# Sheet1.net
KiCad netlist of a schematic drawn in Altium Designer
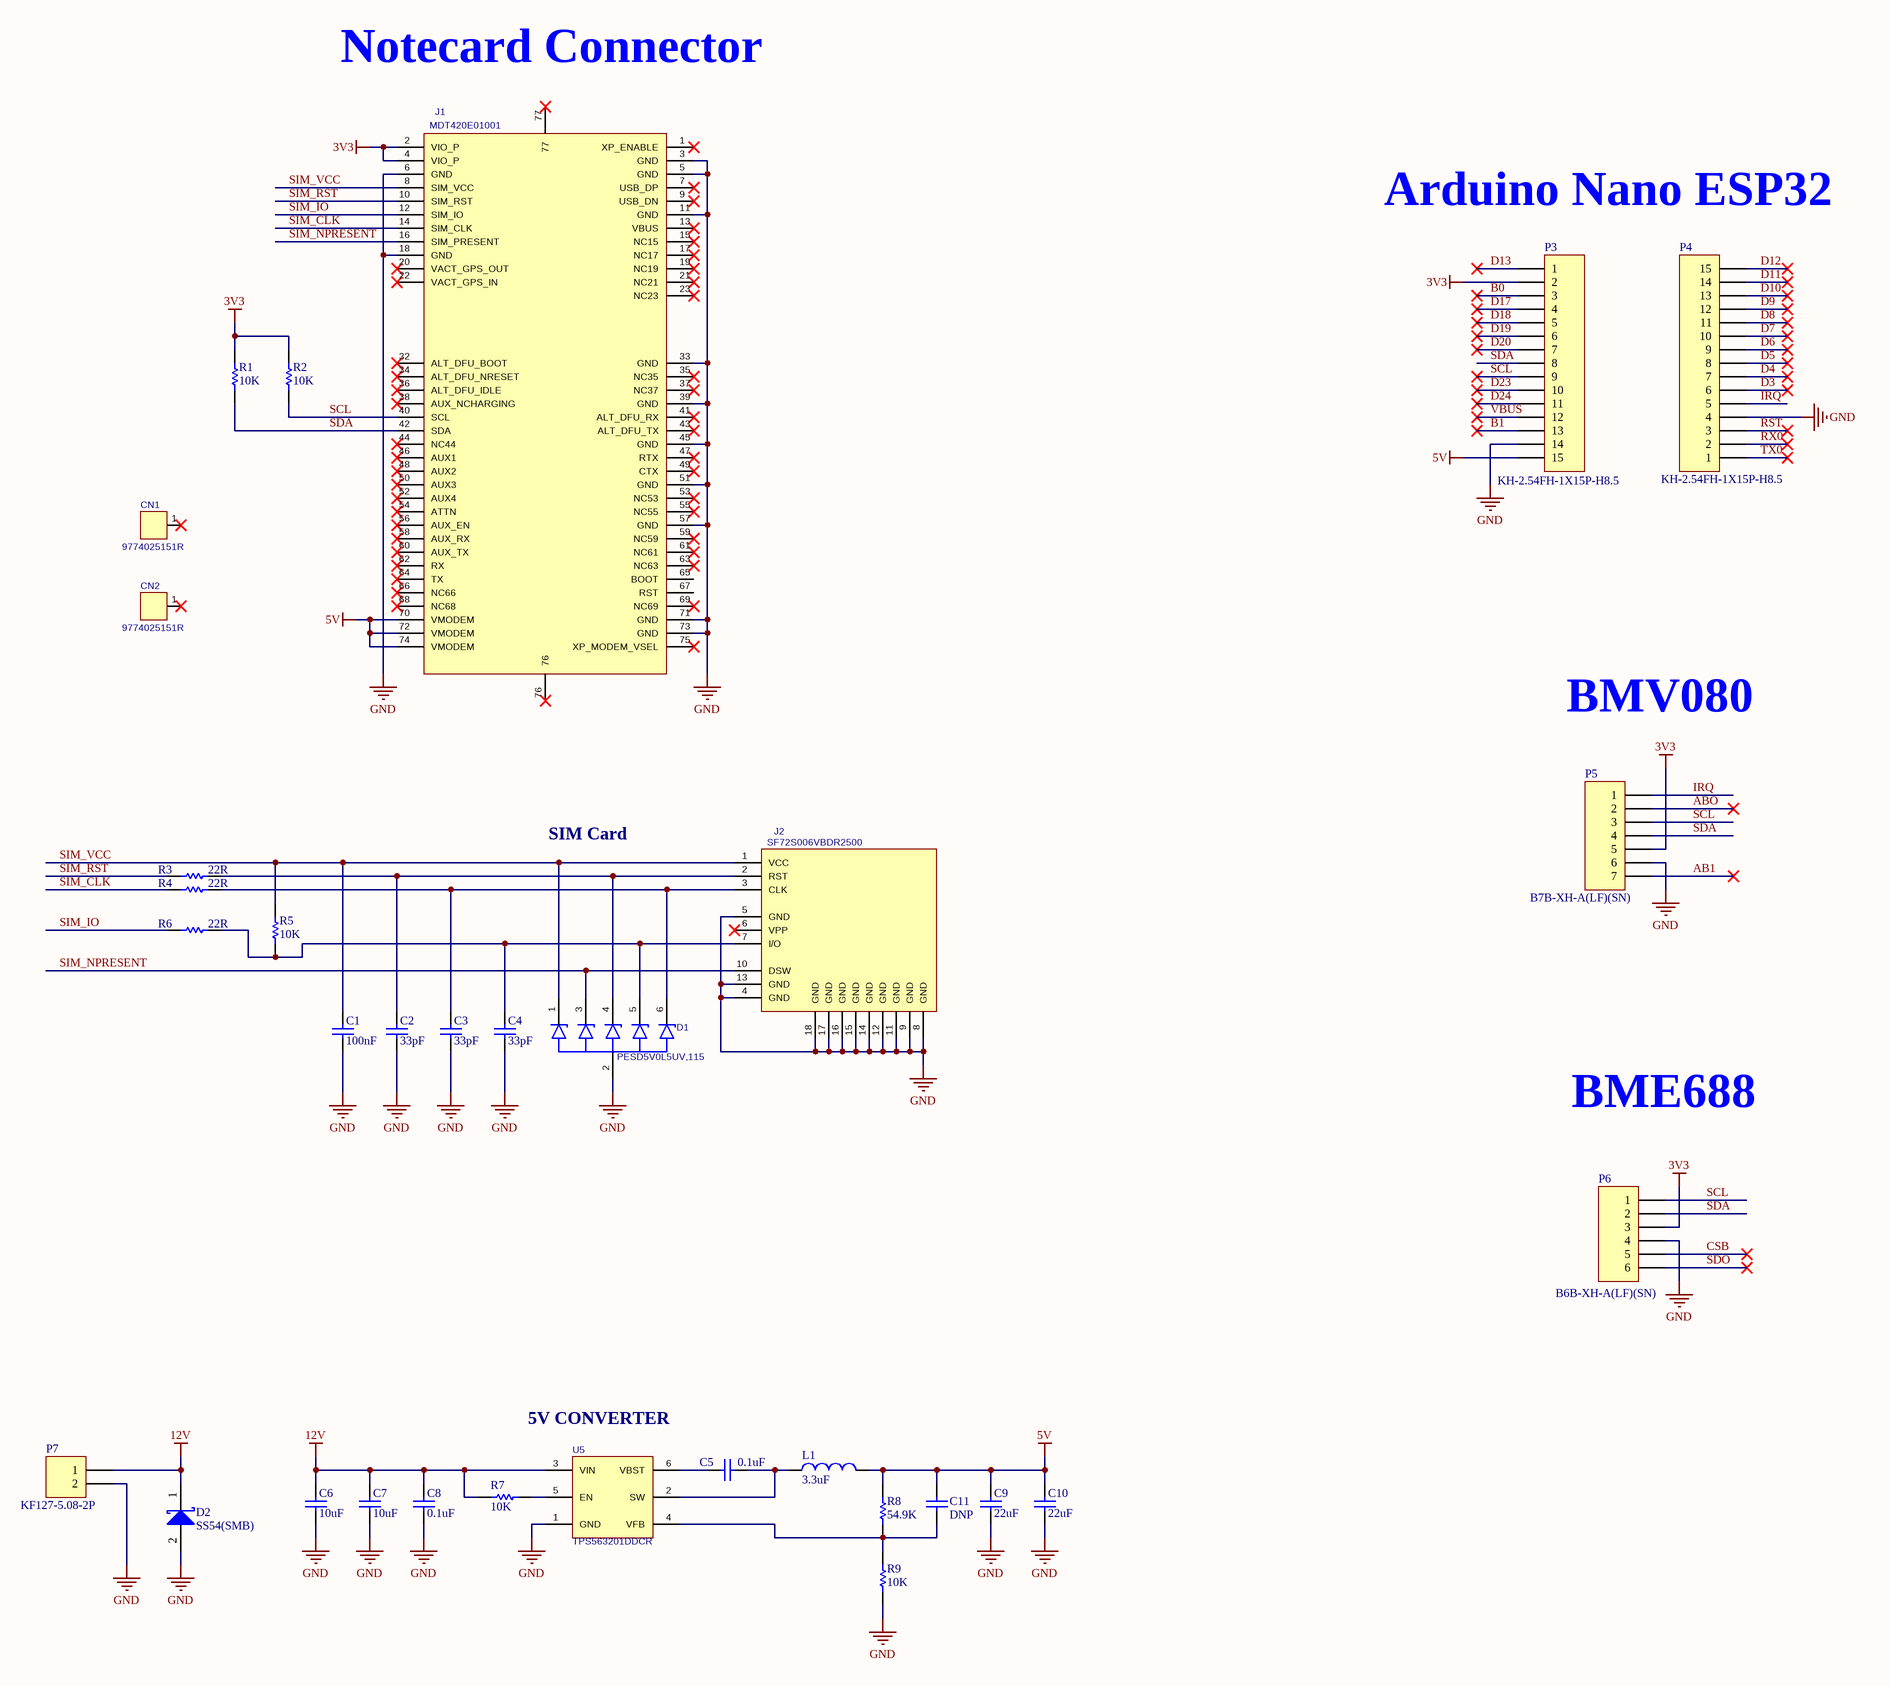
[diagram p0: Sheet1.SchDoc]

(export (version "E")
  (design (tool "Eeschema 10.0.6"))
  (components
    (comp (ref "C1")
      (value "100nF")
      (footprint "Ceramic capacitor (0402)")
      (description "Capacitor")
      (fields (field (name "PART NUMBER") "C1525"))
      (libsource (lib "Guitar_Audio_System") (part "Cap"))
    )
    (comp (ref "C2")
      (value "33pF")
      (footprint "Ceramic capacitor (0402)")
      (description "Capacitor")
      (fields (field (name "PART NUMBER") "C107005"))
      (libsource (lib "Guitar_Audio_System") (part "Cap"))
    )
    (comp (ref "C3")
      (value "33pF")
      (footprint "Ceramic capacitor (0402)")
      (description "Capacitor")
      (fields (field (name "PART NUMBER") "C107005"))
      (libsource (lib "Guitar_Audio_System") (part "Cap"))
    )
    (comp (ref "C4")
      (value "33pF")
      (footprint "Ceramic capacitor (0402)")
      (description "Capacitor")
      (fields (field (name "PART NUMBER") "C107005"))
      (libsource (lib "Guitar_Audio_System") (part "Cap"))
    )
    (comp (ref "C5")
      (value "0.1uF")
      (footprint "Ceramic capacitor (0603)")
      (description "Capacitor")
      (fields (field (name "PART NUMBER") "C14663"))
      (libsource (lib "Guitar_Audio_System") (part "Cap"))
    )
    (comp (ref "C6")
      (value "10uF")
      (footprint "Ceramic capacitor (0805)")
      (description "Capacitor")
      (fields (field (name "PART NUMBER") "C15850"))
      (libsource (lib "Guitar_Audio_System") (part "Cap"))
    )
    (comp (ref "C7")
      (value "10uF")
      (footprint "Ceramic capacitor (0805)")
      (description "Capacitor")
      (fields (field (name "PART NUMBER") "C15850"))
      (libsource (lib "Guitar_Audio_System") (part "Cap"))
    )
    (comp (ref "C8")
      (value "0.1uF")
      (footprint "Ceramic capacitor (0805)")
      (description "Capacitor")
      (fields (field (name "PART NUMBER") "C519981"))
      (libsource (lib "Guitar_Audio_System") (part "Cap"))
    )
    (comp (ref "C9")
      (value "22uF")
      (footprint "Ceramic capacitor (0805)")
      (description "Capacitor")
      (fields (field (name "PART NUMBER") "C296720"))
      (libsource (lib "Guitar_Audio_System") (part "Cap"))
    )
    (comp (ref "C10")
      (value "22uF")
      (footprint "Ceramic capacitor (0805)")
      (description "Capacitor")
      (fields (field (name "PART NUMBER") "C296720"))
      (libsource (lib "Guitar_Audio_System") (part "Cap"))
    )
    (comp (ref "C11")
      (value "DNP")
      (footprint "Ceramic capacitor (0603)")
      (description "Capacitor")
      (libsource (lib "Guitar_Audio_System") (part "Cap"))
    )
    (comp (ref "CN1")
      (value "9774025151R")
      (footprint "SMD-1_BD5.1-D3.5")
      (fields (field (name "PART NUMBER") "C7496631") (field (name "MANUFACTURER") "Wurth(伍尔特)"))
      (libsource (lib "Schlib1") (part "9774025151R_C7496631"))
    )
    (comp (ref "CN2")
      (value "9774025151R")
      (footprint "SMD-1_BD5.1-D3.5")
      (fields (field (name "PART NUMBER") "C7496631") (field (name "MANUFACTURER") "Wurth(伍尔特)"))
      (libsource (lib "Schlib1") (part "9774025151R_C7496631"))
    )
    (comp (ref "D1")
      (value "PESD5V0L5UV,115")
      (footprint "SOT-666-6_L1.6-W1.2-P0.50-LS1.6-TL")
      (fields (field (name "PART NUMBER") "C84255") (field (name "MANUFACTURER") "Nexperia(安世)"))
      (libsource (lib "Schlib1") (part "PESD5V0L5UV,115"))
    )
    (comp (ref "D2")
      (value "SS54(SMB)")
      (footprint "FP_SS54(SMB)")
      (description "Schottky Diode")
      (fields (field (name "PART NUMBER") "C4154972") (field (name "PUBLISHER") "Altium Limited"))
      (libsource (lib "Miscellaneous Devices") (part "D Schottky"))
    )
    (comp (ref "J1")
      (value "MDT420E01001")
      (footprint "CONN-SMD_67P-P0.50_TE_2199119-6")
      (fields (field (name "PART NUMBER") "C4529147") (field (name "MANUFACTURER") "Amphenol"))
      (libsource (lib "Schlib1") (part "MDT420E01001"))
    )
    (comp (ref "J2")
      (value "SF72S006VBDR2500")
      (footprint "NANO-SIM-SMD_SMN-315-ARP7")
      (fields (field (name "PART NUMBER") "C2977286") (field (name "MANUFACTURER") "JAE(日本航空电子)"))
      (libsource (lib "Schlib1") (part "SF72S006VBDR2500"))
    )
    (comp (ref "L1")
      (value "3.3uF")
      (footprint "IND-SMD_L7.3-W6.6")
      (description "Inductor")
      (fields (field (name "PART NUMBER") "C128687") (field (name "PUBLISHER") "Altium Limited"))
      (libsource (lib "Miscellaneous Devices") (part "Inductor"))
    )
    (comp (ref "P3")
      (value "KH-2.54FH-1X15P-H8.5")
      (footprint "HDR-TH_15P-P2.54-V-F")
      (description "Header, 15-Pin")
      (fields (field (name "PART NUMBER") "C2932676") (field (name "PUBLISHER") "Altium Limited"))
      (libsource (lib "") (part "Header 15_1"))
    )
    (comp (ref "P4")
      (value "KH-2.54FH-1X15P-H8.5")
      (footprint "HDR-TH_15P-P2.54-V-F")
      (description "Header, 15-Pin")
      (fields (field (name "PART NUMBER") "C2932676") (field (name "PUBLISHER") "Altium Limited"))
      (libsource (lib "Miscellaneous Connectors") (part "Header 15"))
    )
    (comp (ref "P5")
      (value "B7B-XH-A(LF)(SN)")
      (footprint "CONN-TH_7P-P2.50_B7B-XH-A-LF-SN")
      (fields (field (name "PART NUMBER") "C144398") (field (name "PUBLISHER") "Altium Limited"))
      (libsource (lib "Miscellaneous Connectors") (part "Header 7"))
    )
    (comp (ref "P6")
      (value "B6B-XH-A(LF)(SN)")
      (footprint "CONN-TH_6P-P2.50_B6B-XH-A-LF-SN")
      (fields (field (name "PART NUMBER") "C144397") (field (name "PUBLISHER") "Altium Limited"))
      (libsource (lib "Miscellaneous Connectors") (part "Header 6"))
    )
    (comp (ref "P7")
      (value "KF127-5.08-2P")
      (footprint "CONN-TH_P5.08_KF127-5.08-2P")
      (description "Header, 2-Pin")
      (fields (field (name "PART NUMBER") "C474906") (field (name "PUBLISHER") "Altium Limited"))
      (libsource (lib "Miscellaneous Connectors") (part "Header 2"))
    )
    (comp (ref "R1")
      (value "10K")
      (footprint "Resistor  (0603)")
      (description "Semiconductor Resistor")
      (fields (field (name "PART NUMBER") "C191124"))
      (libsource (lib "ESP32_Audio_Instrument") (part "Res Semi"))
    )
    (comp (ref "R2")
      (value "10K")
      (footprint "Resistor  (0603)")
      (description "Semiconductor Resistor")
      (fields (field (name "PART NUMBER") "C191124"))
      (libsource (lib "ESP32_Audio_Instrument") (part "Res Semi"))
    )
    (comp (ref "R3")
      (value "22R")
      (footprint "Resistor  (0402)")
      (description "Semiconductor Resistor")
      (fields (field (name "PART NUMBER") "C25092"))
      (libsource (lib "ESP32_Audio_Instrument") (part "Res Semi"))
    )
    (comp (ref "R4")
      (value "22R")
      (footprint "Resistor  (0402)")
      (description "Semiconductor Resistor")
      (fields (field (name "PART NUMBER") "C25092"))
      (libsource (lib "ESP32_Audio_Instrument") (part "Res Semi"))
    )
    (comp (ref "R5")
      (value "10K")
      (footprint "Resistor  (0402)")
      (description "Semiconductor Resistor")
      (fields (field (name "PART NUMBER") "C427247"))
      (libsource (lib "ESP32_Audio_Instrument") (part "Res Semi"))
    )
    (comp (ref "R6")
      (value "22R")
      (footprint "Resistor  (0402)")
      (description "Semiconductor Resistor")
      (fields (field (name "PART NUMBER") "C25092"))
      (libsource (lib "ESP32_Audio_Instrument") (part "Res Semi"))
    )
    (comp (ref "R7")
      (value "10K")
      (footprint "Resistor  (0603)")
      (description "Semiconductor Resistor")
      (fields (field (name "PART NUMBER") "C136139"))
      (libsource (lib "ESP32_Audio_Instrument") (part "Res Semi"))
    )
    (comp (ref "R8")
      (value "54.9K")
      (footprint "Resistor  (0603)")
      (description "Semiconductor Resistor")
      (fields (field (name "PART NUMBER") "C185321"))
      (libsource (lib "ESP32_Audio_Instrument") (part "Res Semi"))
    )
    (comp (ref "R9")
      (value "10K")
      (footprint "Resistor  (0603)")
      (description "Semiconductor Resistor")
      (fields (field (name "PART NUMBER") "C130232"))
      (libsource (lib "ESP32_Audio_Instrument") (part "Res Semi"))
    )
    (comp (ref "U5")
      (value "TPS563201DDCR")
      (footprint "SOT-23-6_L2.9-W1.6-P0.95-LS2.8-BR")
      (fields (field (name "PART NUMBER") "C116592") (field (name "MANUFACTURER") "TI(德州仪器)"))
      (libsource (lib "Schlib1") (part "TPS563201DDCR"))
    )
  )
  (nets
    (net (code "1") (name "/AB1") (class "Default")
      (node (ref "P5") (pin "7") (pinfunction "7_7") (pintype "passive+no_connect"))
    )
    (net (code "2") (name "/ABO") (class "Default")
      (node (ref "P5") (pin "2") (pinfunction "2_2") (pintype "passive+no_connect"))
    )
    (net (code "3") (name "/B0") (class "Default")
      (node (ref "P3") (pin "3") (pinfunction "3_3") (pintype "passive+no_connect"))
    )
    (net (code "4") (name "/B1") (class "Default")
      (node (ref "P3") (pin "13") (pinfunction "13_13") (pintype "passive+no_connect"))
    )
    (net (code "5") (name "/CSB") (class "Default")
      (node (ref "P6") (pin "5") (pinfunction "5_5") (pintype "passive+no_connect"))
    )
    (net (code "6") (name "/D3") (class "Default")
      (node (ref "P4") (pin "6") (pinfunction "6_6") (pintype "passive+no_connect"))
    )
    (net (code "7") (name "/D4") (class "Default")
      (node (ref "P4") (pin "7") (pinfunction "7_7") (pintype "passive+no_connect"))
    )
    (net (code "8") (name "/D5") (class "Default")
      (node (ref "P4") (pin "8") (pinfunction "8_8") (pintype "passive+no_connect"))
    )
    (net (code "9") (name "/D6") (class "Default")
      (node (ref "P4") (pin "9") (pinfunction "9_9") (pintype "passive+no_connect"))
    )
    (net (code "10") (name "/D7") (class "Default")
      (node (ref "P4") (pin "10") (pinfunction "10_10") (pintype "passive+no_connect"))
    )
    (net (code "11") (name "/D8") (class "Default")
      (node (ref "P4") (pin "11") (pinfunction "11_11") (pintype "passive+no_connect"))
    )
    (net (code "12") (name "/D9") (class "Default")
      (node (ref "P4") (pin "12") (pinfunction "12_12") (pintype "passive+no_connect"))
    )
    (net (code "13") (name "/D10") (class "Default")
      (node (ref "P4") (pin "13") (pinfunction "13_13") (pintype "passive+no_connect"))
    )
    (net (code "14") (name "/D11") (class "Default")
      (node (ref "P4") (pin "14") (pinfunction "14_14") (pintype "passive+no_connect"))
    )
    (net (code "15") (name "/D12") (class "Default")
      (node (ref "P4") (pin "15") (pinfunction "15_15") (pintype "passive+no_connect"))
    )
    (net (code "16") (name "/D13") (class "Default")
      (node (ref "P3") (pin "1") (pinfunction "1_1") (pintype "passive+no_connect"))
    )
    (net (code "17") (name "/D17") (class "Default")
      (node (ref "P3") (pin "4") (pinfunction "4_4") (pintype "passive+no_connect"))
    )
    (net (code "18") (name "/D18") (class "Default")
      (node (ref "P3") (pin "5") (pinfunction "5_5") (pintype "passive+no_connect"))
    )
    (net (code "19") (name "/D19") (class "Default")
      (node (ref "P3") (pin "6") (pinfunction "6_6") (pintype "passive+no_connect"))
    )
    (net (code "20") (name "/D20") (class "Default")
      (node (ref "P3") (pin "7") (pinfunction "7_7") (pintype "passive+no_connect"))
    )
    (net (code "21") (name "/D23") (class "Default")
      (node (ref "P3") (pin "10") (pinfunction "10_10") (pintype "passive+no_connect"))
    )
    (net (code "22") (name "/D24") (class "Default")
      (node (ref "P3") (pin "11") (pinfunction "11_11") (pintype "passive+no_connect"))
    )
    (net (code "23") (name "/IRQ") (class "Default")
      (node (ref "P4") (pin "5") (pinfunction "5_5") (pintype "passive"))
      (node (ref "P5") (pin "1") (pinfunction "1_1") (pintype "passive"))
    )
    (net (code "24") (name "/RST") (class "Default")
      (node (ref "P4") (pin "3") (pinfunction "3_3") (pintype "passive+no_connect"))
    )
    (net (code "25") (name "/RX0") (class "Default")
      (node (ref "P4") (pin "2") (pinfunction "2_2") (pintype "passive+no_connect"))
    )
    (net (code "26") (name "/SCL") (class "Default")
      (node (ref "J1") (pin "40") (pinfunction "SCL_40") (pintype "passive"))
      (node (ref "P3") (pin "9") (pinfunction "9_9") (pintype "passive"))
      (node (ref "P5") (pin "3") (pinfunction "3_3") (pintype "passive"))
      (node (ref "P6") (pin "1") (pinfunction "1_1") (pintype "passive"))
      (node (ref "R2") (pin "1") (pinfunction "1_1") (pintype "passive"))
    )
    (net (code "27") (name "/SDA") (class "Default")
      (node (ref "J1") (pin "42") (pinfunction "SDA_42") (pintype "passive"))
      (node (ref "P3") (pin "8") (pinfunction "8_8") (pintype "passive"))
      (node (ref "P5") (pin "4") (pinfunction "4_4") (pintype "passive"))
      (node (ref "P6") (pin "2") (pinfunction "2_2") (pintype "passive"))
      (node (ref "R1") (pin "1") (pinfunction "1_1") (pintype "passive"))
    )
    (net (code "28") (name "/SDO") (class "Default")
      (node (ref "P6") (pin "6") (pinfunction "6_6") (pintype "passive+no_connect"))
    )
    (net (code "29") (name "/SIM_CLK") (class "Default")
      (node (ref "J1") (pin "14") (pinfunction "SIM_CLK_14") (pintype "passive"))
      (node (ref "R4") (pin "1") (pinfunction "1_1") (pintype "passive"))
    )
    (net (code "30") (name "/SIM_IO") (class "Default")
      (node (ref "J1") (pin "12") (pinfunction "SIM_IO_12") (pintype "passive"))
      (node (ref "R6") (pin "1") (pinfunction "1_1") (pintype "passive"))
    )
    (net (code "31") (name "/SIM_NPRESENT") (class "Default")
      (node (ref "D1") (pin "3") (pinfunction "3_3") (pintype "passive"))
      (node (ref "J1") (pin "16") (pinfunction "SIM_PRESENT_16") (pintype "passive"))
      (node (ref "J2") (pin "10") (pinfunction "DSW_10") (pintype "passive"))
    )
    (net (code "32") (name "/SIM_RST") (class "Default")
      (node (ref "J1") (pin "10") (pinfunction "SIM_RST_10") (pintype "passive"))
      (node (ref "R3") (pin "1") (pinfunction "1_1") (pintype "passive"))
    )
    (net (code "33") (name "/SIM_VCC") (class "Default")
      (node (ref "C1") (pin "1") (pinfunction "1_1") (pintype "passive"))
      (node (ref "D1") (pin "1") (pinfunction "1_1") (pintype "passive"))
      (node (ref "J1") (pin "8") (pinfunction "SIM_VCC_8") (pintype "passive"))
      (node (ref "J2") (pin "1") (pinfunction "VCC_1") (pintype "passive"))
      (node (ref "R5") (pin "2") (pinfunction "2_2") (pintype "passive"))
    )
    (net (code "34") (name "/TX0") (class "Default")
      (node (ref "P4") (pin "1") (pinfunction "1_1") (pintype "passive+no_connect"))
    )
    (net (code "35") (name "/VBUS") (class "Default")
      (node (ref "P3") (pin "12") (pinfunction "12_12") (pintype "passive+no_connect"))
    )
    (net (code "36") (name "3V3") (class "Default")
      (node (ref "J1") (pin "2") (pinfunction "VIO_P_2") (pintype "passive"))
      (node (ref "J1") (pin "4") (pinfunction "VIO_P_4") (pintype "passive"))
      (node (ref "P3") (pin "2") (pinfunction "2_2") (pintype "passive"))
      (node (ref "P5") (pin "5") (pinfunction "5_5") (pintype "passive"))
      (node (ref "P6") (pin "3") (pinfunction "3_3") (pintype "passive"))
      (node (ref "R1") (pin "2") (pinfunction "2_2") (pintype "passive"))
      (node (ref "R2") (pin "2") (pinfunction "2_2") (pintype "passive"))
    )
    (net (code "37") (name "5V") (class "Default")
      (node (ref "C10") (pin "1") (pinfunction "1_1") (pintype "passive"))
      (node (ref "C11") (pin "2") (pinfunction "2_2") (pintype "passive"))
      (node (ref "C9") (pin "1") (pinfunction "1_1") (pintype "passive"))
      (node (ref "J1") (pin "70") (pinfunction "VMODEM_70") (pintype "passive"))
      (node (ref "J1") (pin "72") (pinfunction "VMODEM_72") (pintype "passive"))
      (node (ref "J1") (pin "74") (pinfunction "VMODEM_74") (pintype "passive"))
      (node (ref "L1") (pin "2") (pinfunction "2_2") (pintype "passive"))
      (node (ref "P3") (pin "15") (pinfunction "15_15") (pintype "passive"))
      (node (ref "R8") (pin "2") (pinfunction "2_2") (pintype "passive"))
    )
    (net (code "38") (name "12V") (class "Default")
      (node (ref "C6") (pin "1") (pinfunction "1_1") (pintype "passive"))
      (node (ref "C7") (pin "1") (pinfunction "1_1") (pintype "passive"))
      (node (ref "C8") (pin "1") (pinfunction "1_1") (pintype "passive"))
      (node (ref "D2") (pin "1") (pinfunction "K_1") (pintype "passive"))
      (node (ref "P7") (pin "1") (pinfunction "1_1") (pintype "passive"))
      (node (ref "R7") (pin "1") (pinfunction "1_1") (pintype "passive"))
      (node (ref "U5") (pin "3") (pinfunction "VIN_3") (pintype "passive"))
    )
    (net (code "39") (name "GND") (class "Default")
      (node (ref "C1") (pin "2") (pinfunction "2_2") (pintype "passive"))
      (node (ref "C10") (pin "2") (pinfunction "2_2") (pintype "passive"))
      (node (ref "C2") (pin "2") (pinfunction "2_2") (pintype "passive"))
      (node (ref "C3") (pin "2") (pinfunction "2_2") (pintype "passive"))
      (node (ref "C4") (pin "2") (pinfunction "2_2") (pintype "passive"))
      (node (ref "C6") (pin "2") (pinfunction "2_2") (pintype "passive"))
      (node (ref "C7") (pin "2") (pinfunction "2_2") (pintype "passive"))
      (node (ref "C8") (pin "2") (pinfunction "2_2") (pintype "passive"))
      (node (ref "C9") (pin "2") (pinfunction "2_2") (pintype "passive"))
      (node (ref "D1") (pin "2") (pinfunction "2_2") (pintype "passive"))
      (node (ref "D2") (pin "2") (pinfunction "A_2") (pintype "passive"))
      (node (ref "J1") (pin "11") (pinfunction "GND_11") (pintype "passive"))
      (node (ref "J1") (pin "18") (pinfunction "GND_18") (pintype "passive"))
      (node (ref "J1") (pin "3") (pinfunction "GND_3") (pintype "passive"))
      (node (ref "J1") (pin "33") (pinfunction "GND_33") (pintype "passive"))
      (node (ref "J1") (pin "39") (pinfunction "GND_39") (pintype "passive"))
      (node (ref "J1") (pin "45") (pinfunction "GND_45") (pintype "passive"))
      (node (ref "J1") (pin "5") (pinfunction "GND_5") (pintype "passive"))
      (node (ref "J1") (pin "51") (pinfunction "GND_51") (pintype "passive"))
      (node (ref "J1") (pin "57") (pinfunction "GND_57") (pintype "passive"))
      (node (ref "J1") (pin "6") (pinfunction "GND_6") (pintype "passive"))
      (node (ref "J1") (pin "71") (pinfunction "GND_71") (pintype "passive"))
      (node (ref "J1") (pin "73") (pinfunction "GND_73") (pintype "passive"))
      (node (ref "J2") (pin "11") (pinfunction "GND_11") (pintype "passive"))
      (node (ref "J2") (pin "12") (pinfunction "GND_12") (pintype "passive"))
      (node (ref "J2") (pin "13") (pinfunction "GND_13") (pintype "passive"))
      (node (ref "J2") (pin "14") (pinfunction "GND_14") (pintype "passive"))
      (node (ref "J2") (pin "15") (pinfunction "GND_15") (pintype "passive"))
      (node (ref "J2") (pin "16") (pinfunction "GND_16") (pintype "passive"))
      (node (ref "J2") (pin "17") (pinfunction "GND_17") (pintype "passive"))
      (node (ref "J2") (pin "18") (pinfunction "GND_18") (pintype "passive"))
      (node (ref "J2") (pin "4") (pinfunction "GND_4") (pintype "passive"))
      (node (ref "J2") (pin "5") (pinfunction "GND_5") (pintype "passive"))
      (node (ref "J2") (pin "8") (pinfunction "GND_8") (pintype "passive"))
      (node (ref "J2") (pin "9") (pinfunction "GND_9") (pintype "passive"))
      (node (ref "P3") (pin "14") (pinfunction "14_14") (pintype "passive"))
      (node (ref "P4") (pin "4") (pinfunction "4_4") (pintype "passive"))
      (node (ref "P5") (pin "6") (pinfunction "6_6") (pintype "passive"))
      (node (ref "P6") (pin "4") (pinfunction "4_4") (pintype "passive"))
      (node (ref "P7") (pin "2") (pinfunction "2_2") (pintype "passive"))
      (node (ref "R9") (pin "1") (pinfunction "1_1") (pintype "passive"))
      (node (ref "U5") (pin "1") (pinfunction "GND_1") (pintype "passive"))
    )
    (net (code "40") (name "Net-(J2-CLK)") (class "Default")
      (node (ref "C3") (pin "1") (pinfunction "1_1") (pintype "passive"))
      (node (ref "D1") (pin "6") (pinfunction "6_6") (pintype "passive"))
      (node (ref "J2") (pin "3") (pinfunction "CLK_3") (pintype "passive"))
      (node (ref "R4") (pin "2") (pinfunction "2_2") (pintype "passive"))
    )
    (net (code "41") (name "Net-(J2-I{slash}O)") (class "Default")
      (node (ref "C4") (pin "1") (pinfunction "1_1") (pintype "passive"))
      (node (ref "D1") (pin "5") (pinfunction "5_5") (pintype "passive"))
      (node (ref "J2") (pin "7") (pinfunction "I/O_7") (pintype "passive"))
      (node (ref "R5") (pin "1") (pinfunction "1_1") (pintype "passive"))
      (node (ref "R6") (pin "2") (pinfunction "2_2") (pintype "passive"))
    )
    (net (code "42") (name "Net-(J2-RST)") (class "Default")
      (node (ref "C2") (pin "1") (pinfunction "1_1") (pintype "passive"))
      (node (ref "D1") (pin "4") (pinfunction "4_4") (pintype "passive"))
      (node (ref "J2") (pin "2") (pinfunction "RST_2") (pintype "passive"))
      (node (ref "R3") (pin "2") (pinfunction "2_2") (pintype "passive"))
    )
    (net (code "43") (name "Net-(U5-EN)") (class "Default")
      (node (ref "R7") (pin "2") (pinfunction "2_2") (pintype "passive"))
      (node (ref "U5") (pin "5") (pinfunction "EN_5") (pintype "passive"))
    )
    (net (code "44") (name "Net-(U5-SW)") (class "Default")
      (node (ref "C5") (pin "1") (pinfunction "1_1") (pintype "passive"))
      (node (ref "L1") (pin "1") (pinfunction "1_1") (pintype "passive"))
      (node (ref "U5") (pin "2") (pinfunction "SW_2") (pintype "passive"))
    )
    (net (code "45") (name "Net-(U5-VBST)") (class "Default")
      (node (ref "C5") (pin "2") (pinfunction "2_2") (pintype "passive"))
      (node (ref "U5") (pin "6") (pinfunction "VBST_6") (pintype "passive"))
    )
    (net (code "46") (name "Net-(U5-VFB)") (class "Default")
      (node (ref "C11") (pin "1") (pinfunction "1_1") (pintype "passive"))
      (node (ref "R8") (pin "1") (pinfunction "1_1") (pintype "passive"))
      (node (ref "R9") (pin "2") (pinfunction "2_2") (pintype "passive"))
      (node (ref "U5") (pin "4") (pinfunction "VFB_4") (pintype "passive"))
    )
    (net (code "47") (name "unconnected-(CN1-Pad1)") (class "Default")
      (node (ref "CN1") (pin "1") (pinfunction "1_1") (pintype "passive+no_connect"))
    )
    (net (code "48") (name "unconnected-(CN2-Pad1)") (class "Default")
      (node (ref "CN2") (pin "1") (pinfunction "1_1") (pintype "passive+no_connect"))
    )
    (net (code "49") (name "unconnected-(J1-ALT_DFU_BOOT-Pad32)") (class "Default")
      (node (ref "J1") (pin "32") (pinfunction "ALT_DFU_BOOT_32") (pintype "passive+no_connect"))
    )
    (net (code "50") (name "unconnected-(J1-ALT_DFU_IDLE-Pad36)") (class "Default")
      (node (ref "J1") (pin "36") (pinfunction "ALT_DFU_IDLE_36") (pintype "passive+no_connect"))
    )
    (net (code "51") (name "unconnected-(J1-ALT_DFU_NRESET-Pad34)") (class "Default")
      (node (ref "J1") (pin "34") (pinfunction "ALT_DFU_NRESET_34") (pintype "passive+no_connect"))
    )
    (net (code "52") (name "unconnected-(J1-ALT_DFU_RX-Pad41)") (class "Default")
      (node (ref "J1") (pin "41") (pinfunction "ALT_DFU_RX_41") (pintype "passive+no_connect"))
    )
    (net (code "53") (name "unconnected-(J1-ALT_DFU_TX-Pad43)") (class "Default")
      (node (ref "J1") (pin "43") (pinfunction "ALT_DFU_TX_43") (pintype "passive+no_connect"))
    )
    (net (code "54") (name "unconnected-(J1-ATTN-Pad54)") (class "Default")
      (node (ref "J1") (pin "54") (pinfunction "ATTN_54") (pintype "passive+no_connect"))
    )
    (net (code "55") (name "unconnected-(J1-AUX1-Pad46)") (class "Default")
      (node (ref "J1") (pin "46") (pinfunction "AUX1_46") (pintype "passive+no_connect"))
    )
    (net (code "56") (name "unconnected-(J1-AUX2-Pad48)") (class "Default")
      (node (ref "J1") (pin "48") (pinfunction "AUX2_48") (pintype "passive+no_connect"))
    )
    (net (code "57") (name "unconnected-(J1-AUX3-Pad50)") (class "Default")
      (node (ref "J1") (pin "50") (pinfunction "AUX3_50") (pintype "passive+no_connect"))
    )
    (net (code "58") (name "unconnected-(J1-AUX4-Pad52)") (class "Default")
      (node (ref "J1") (pin "52") (pinfunction "AUX4_52") (pintype "passive+no_connect"))
    )
    (net (code "59") (name "unconnected-(J1-AUX_EN-Pad56)") (class "Default")
      (node (ref "J1") (pin "56") (pinfunction "AUX_EN_56") (pintype "passive+no_connect"))
    )
    (net (code "60") (name "unconnected-(J1-AUX_NCHARGING-Pad38)") (class "Default")
      (node (ref "J1") (pin "38") (pinfunction "AUX_NCHARGING_38") (pintype "passive+no_connect"))
    )
    (net (code "61") (name "unconnected-(J1-AUX_RX-Pad58)") (class "Default")
      (node (ref "J1") (pin "58") (pinfunction "AUX_RX_58") (pintype "passive+no_connect"))
    )
    (net (code "62") (name "unconnected-(J1-AUX_TX-Pad60)") (class "Default")
      (node (ref "J1") (pin "60") (pinfunction "AUX_TX_60") (pintype "passive+no_connect"))
    )
    (net (code "63") (name "unconnected-(J1-BOOT-Pad65)") (class "Default")
      (node (ref "J1") (pin "65") (pinfunction "BOOT_65") (pintype "passive"))
    )
    (net (code "64") (name "unconnected-(J1-CTX-Pad49)") (class "Default")
      (node (ref "J1") (pin "49") (pinfunction "CTX_49") (pintype "passive+no_connect"))
    )
    (net (code "65") (name "unconnected-(J1-NC15-Pad15)") (class "Default")
      (node (ref "J1") (pin "15") (pinfunction "NC15_15") (pintype "passive+no_connect"))
    )
    (net (code "66") (name "unconnected-(J1-NC17-Pad17)") (class "Default")
      (node (ref "J1") (pin "17") (pinfunction "NC17_17") (pintype "passive+no_connect"))
    )
    (net (code "67") (name "unconnected-(J1-NC19-Pad19)") (class "Default")
      (node (ref "J1") (pin "19") (pinfunction "NC19_19") (pintype "passive+no_connect"))
    )
    (net (code "68") (name "unconnected-(J1-NC21-Pad21)") (class "Default")
      (node (ref "J1") (pin "21") (pinfunction "NC21_21") (pintype "passive+no_connect"))
    )
    (net (code "69") (name "unconnected-(J1-NC23-Pad23)") (class "Default")
      (node (ref "J1") (pin "23") (pinfunction "NC23_23") (pintype "passive+no_connect"))
    )
    (net (code "70") (name "unconnected-(J1-NC35-Pad35)") (class "Default")
      (node (ref "J1") (pin "35") (pinfunction "NC35_35") (pintype "passive+no_connect"))
    )
    (net (code "71") (name "unconnected-(J1-NC37-Pad37)") (class "Default")
      (node (ref "J1") (pin "37") (pinfunction "NC37_37") (pintype "passive+no_connect"))
    )
    (net (code "72") (name "unconnected-(J1-NC44-Pad44)") (class "Default")
      (node (ref "J1") (pin "44") (pinfunction "NC44_44") (pintype "passive+no_connect"))
    )
    (net (code "73") (name "unconnected-(J1-NC53-Pad53)") (class "Default")
      (node (ref "J1") (pin "53") (pinfunction "NC53_53") (pintype "passive+no_connect"))
    )
    (net (code "74") (name "unconnected-(J1-NC55-Pad55)") (class "Default")
      (node (ref "J1") (pin "55") (pinfunction "NC55_55") (pintype "passive+no_connect"))
    )
    (net (code "75") (name "unconnected-(J1-NC59-Pad59)") (class "Default")
      (node (ref "J1") (pin "59") (pinfunction "NC59_59") (pintype "passive+no_connect"))
    )
    (net (code "76") (name "unconnected-(J1-NC61-Pad61)") (class "Default")
      (node (ref "J1") (pin "61") (pinfunction "NC61_61") (pintype "passive+no_connect"))
    )
    (net (code "77") (name "unconnected-(J1-NC63-Pad63)") (class "Default")
      (node (ref "J1") (pin "63") (pinfunction "NC63_63") (pintype "passive+no_connect"))
    )
    (net (code "78") (name "unconnected-(J1-NC66-Pad66)") (class "Default")
      (node (ref "J1") (pin "66") (pinfunction "NC66_66") (pintype "passive+no_connect"))
    )
    (net (code "79") (name "unconnected-(J1-NC68-Pad68)") (class "Default")
      (node (ref "J1") (pin "68") (pinfunction "NC68_68") (pintype "passive+no_connect"))
    )
    (net (code "80") (name "unconnected-(J1-NC69-Pad69)") (class "Default")
      (node (ref "J1") (pin "69") (pinfunction "NC69_69") (pintype "passive+no_connect"))
    )
    (net (code "81") (name "unconnected-(J1-Pad76)") (class "Default")
      (node (ref "J1") (pin "76") (pinfunction "76_76") (pintype "passive+no_connect"))
    )
    (net (code "82") (name "unconnected-(J1-Pad77)") (class "Default")
      (node (ref "J1") (pin "77") (pinfunction "77_77") (pintype "passive+no_connect"))
    )
    (net (code "83") (name "unconnected-(J1-RST-Pad67)") (class "Default")
      (node (ref "J1") (pin "67") (pinfunction "RST_67") (pintype "passive"))
    )
    (net (code "84") (name "unconnected-(J1-RTX-Pad47)") (class "Default")
      (node (ref "J1") (pin "47") (pinfunction "RTX_47") (pintype "passive+no_connect"))
    )
    (net (code "85") (name "unconnected-(J1-RX-Pad62)") (class "Default")
      (node (ref "J1") (pin "62") (pinfunction "RX_62") (pintype "passive+no_connect"))
    )
    (net (code "86") (name "unconnected-(J1-TX-Pad64)") (class "Default")
      (node (ref "J1") (pin "64") (pinfunction "TX_64") (pintype "passive+no_connect"))
    )
    (net (code "87") (name "unconnected-(J1-USB_DN-Pad9)") (class "Default")
      (node (ref "J1") (pin "9") (pinfunction "USB_DN_9") (pintype "passive+no_connect"))
    )
    (net (code "88") (name "unconnected-(J1-USB_DP-Pad7)") (class "Default")
      (node (ref "J1") (pin "7") (pinfunction "USB_DP_7") (pintype "passive+no_connect"))
    )
    (net (code "89") (name "unconnected-(J1-VACT_GPS_IN-Pad22)") (class "Default")
      (node (ref "J1") (pin "22") (pinfunction "VACT_GPS_IN_22") (pintype "passive+no_connect"))
    )
    (net (code "90") (name "unconnected-(J1-VACT_GPS_OUT-Pad20)") (class "Default")
      (node (ref "J1") (pin "20") (pinfunction "VACT_GPS_OUT_20") (pintype "passive+no_connect"))
    )
    (net (code "91") (name "unconnected-(J1-VBUS-Pad13)") (class "Default")
      (node (ref "J1") (pin "13") (pinfunction "VBUS_13") (pintype "passive+no_connect"))
    )
    (net (code "92") (name "unconnected-(J1-XP_ENABLE-Pad1)") (class "Default")
      (node (ref "J1") (pin "1") (pinfunction "XP_ENABLE_1") (pintype "passive+no_connect"))
    )
    (net (code "93") (name "unconnected-(J1-XP_MODEM_VSEL-Pad75)") (class "Default")
      (node (ref "J1") (pin "75") (pinfunction "XP_MODEM_VSEL_75") (pintype "passive+no_connect"))
    )
    (net (code "94") (name "unconnected-(J2-VPP-Pad6)") (class "Default")
      (node (ref "J2") (pin "6") (pinfunction "VPP_6") (pintype "passive+no_connect"))
    )
  )
)
